# SendClient_Sheet.net
KiCad netlist of a schematic drawn in Altium Designer
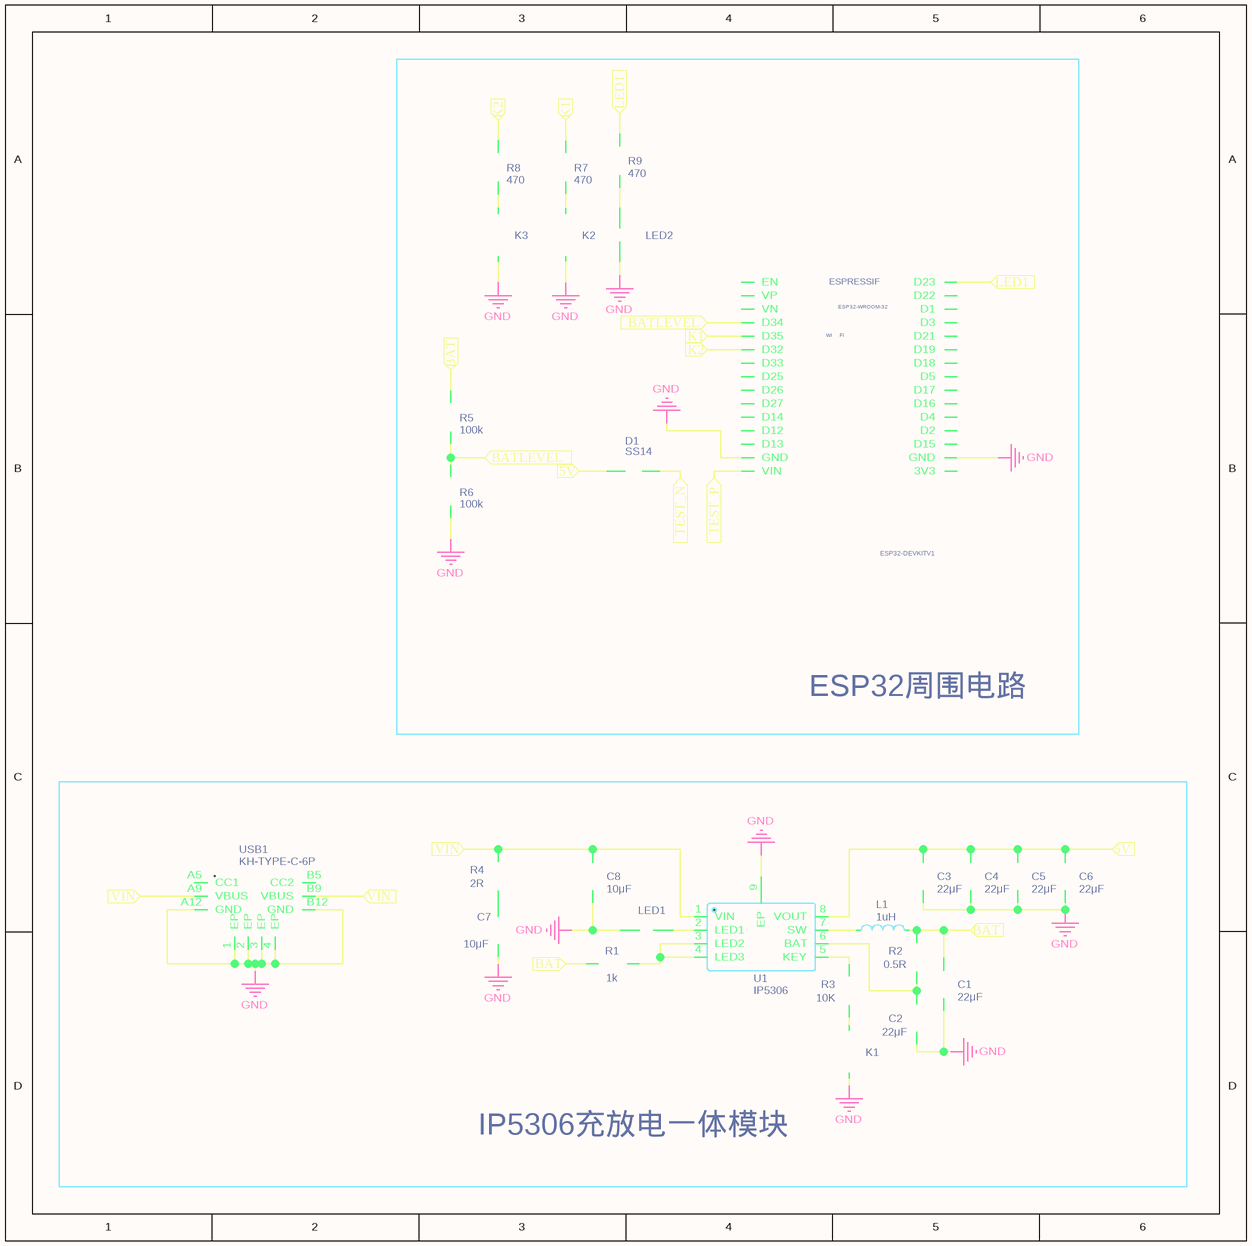
[diagram p0: SendClient_Sheet.schdoc]

(export (version "E")
  (design (tool "Eeschema 10.0.6"))
  (components
    (comp (ref "BOARD1")
      (value "ESP32DEVKITV1")
      (fields (field (name "CONTRIBUTOR") "radio"))
      (libsource (lib "altium-import") (part "root_0_ESP32DEVKITV1_"))
    )
    (comp (ref "C1")
      (value "22μF")
      (fields
        (field (name "BOM_SUPPLIER PART") "C338150")
        (field (name "BOM_MANUFACTURER PART") "0603B101K500CT")
        (field (name "CONTRIBUTOR") "LCSC")
      )
      (libsource (lib "altium-import") (part "root_3_22μF_"))
    )
    (comp (ref "C2")
      (value "22μF")
      (fields
        (field (name "BOM_SUPPLIER PART") "C338150")
        (field (name "BOM_MANUFACTURER PART") "0603B101K500CT")
        (field (name "CONTRIBUTOR") "LCSC")
      )
      (libsource (lib "altium-import") (part "root_3_22μF_"))
    )
    (comp (ref "C3")
      (value "22μF")
      (fields
        (field (name "BOM_SUPPLIER PART") "C338150")
        (field (name "BOM_MANUFACTURER PART") "0603B101K500CT")
        (field (name "CONTRIBUTOR") "LCSC")
      )
      (libsource (lib "altium-import") (part "root_3_22μF_"))
    )
    (comp (ref "C4")
      (value "22μF")
      (fields
        (field (name "BOM_SUPPLIER PART") "C338150")
        (field (name "BOM_MANUFACTURER PART") "0603B101K500CT")
        (field (name "CONTRIBUTOR") "LCSC")
      )
      (libsource (lib "altium-import") (part "root_3_22μF_"))
    )
    (comp (ref "C5")
      (value "22μF")
      (fields
        (field (name "BOM_SUPPLIER PART") "C338150")
        (field (name "BOM_MANUFACTURER PART") "0603B101K500CT")
        (field (name "CONTRIBUTOR") "LCSC")
      )
      (libsource (lib "altium-import") (part "root_3_22μF_"))
    )
    (comp (ref "C6")
      (value "22μF")
      (fields
        (field (name "BOM_SUPPLIER PART") "C338150")
        (field (name "BOM_MANUFACTURER PART") "0603B101K500CT")
        (field (name "CONTRIBUTOR") "LCSC")
      )
      (libsource (lib "altium-import") (part "root_3_22μF_"))
    )
    (comp (ref "C7")
      (value "10μF")
      (fields
        (field (name "BOM_SUPPLIER PART") "C338150")
        (field (name "BOM_MANUFACTURER PART") "0603B101K500CT")
        (field (name "CONTRIBUTOR") "LCSC")
      )
      (libsource (lib "altium-import") (part "root_3_10μF_"))
    )
    (comp (ref "C8")
      (value "10μF")
      (fields
        (field (name "BOM_SUPPLIER PART") "C338150")
        (field (name "BOM_MANUFACTURER PART") "0603B101K500CT")
        (field (name "CONTRIBUTOR") "LCSC")
      )
      (libsource (lib "altium-import") (part "root_3_10μF_"))
    )
    (comp (ref "D1")
      (value "SS14")
      (fields (field (name "BOM_SUPPLIER PART") "C2480"))
      (libsource (lib "altium-import") (part "root_2_SS14_"))
    )
    (comp (ref "K1")
      (value "BUTTON_FLASH")
      (fields (field (name "CONTRIBUTOR") "dingding1"))
      (libsource (lib "altium-import") (part "root_3_BUTTON_FLASH_"))
    )
    (comp (ref "K2")
      (value "BUTTON_FLASH")
      (fields (field (name "CONTRIBUTOR") "dingding1"))
      (libsource (lib "altium-import") (part "root_3_BUTTON_FLASH_"))
    )
    (comp (ref "K3")
      (value "BUTTON_FLASH")
      (fields (field (name "CONTRIBUTOR") "dingding1"))
      (libsource (lib "altium-import") (part "root_3_BUTTON_FLASH_"))
    )
    (comp (ref "L1")
      (value "1uH")
      (fields
        (field (name "BOM_SUPPLIER PART") "C436543")
        (field (name "BOM_MANUFACTURER PART") "PSPMAA0603-1R0M-ANF")
        (field (name "CONTRIBUTOR") "LCSC")
      )
      (libsource (lib "altium-import") (part "root_0_1uH_"))
    )
    (comp (ref "LED1")
      (value "LED-0603_R")
      (fields
        (field (name "BOM_MANUFACTURER PART") "19-217/R6C-AL1M2VY/3T")
        (field (name "BOM_SUPPLIER PART") "C72044")
        (field (name "CONTRIBUTOR") "LCEDA_01")
      )
      (libsource (lib "altium-import") (part "root_2_LED-0603_R_"))
    )
    (comp (ref "LED2")
      (value "LED-0603_R")
      (fields
        (field (name "BOM_MANUFACTURER PART") "19-217/R6C-AL1M2VY/3T")
        (field (name "BOM_SUPPLIER PART") "C72044")
        (field (name "CONTRIBUTOR") "LCEDA_01")
      )
      (libsource (lib "altium-import") (part "root_3_LED-0603_R_"))
    )
    (comp (ref "R1")
      (value "1k")
      (fields
        (field (name "BOM_MANUFACTURER PART") "RC0603JR-079K1L")
        (field (name "BOM_SUPPLIER PART") "C137602")
      )
      (libsource (lib "altium-import") (part "root_2_1k_"))
    )
    (comp (ref "R2")
      (value "0.5R")
      (fields
        (field (name "BOM_MANUFACTURER PART") "RC0603JR-079K1L")
        (field (name "BOM_SUPPLIER PART") "C137602")
      )
      (libsource (lib "altium-import") (part "root_3_0.5R_"))
    )
    (comp (ref "R3")
      (value "10K")
      (fields
        (field (name "BOM_MANUFACTURER PART") "RC0603JR-079K1L")
        (field (name "BOM_SUPPLIER PART") "C137602")
      )
      (libsource (lib "altium-import") (part "root_3_10K_"))
    )
    (comp (ref "R4")
      (value "2R")
      (fields
        (field (name "BOM_MANUFACTURER PART") "RC0603JR-079K1L")
        (field (name "BOM_SUPPLIER PART") "C137602")
      )
      (libsource (lib "altium-import") (part "root_3_2R_"))
    )
    (comp (ref "R5")
      (value "100k")
      (fields
        (field (name "BOM_MANUFACTURER PART") "RC0603JR-079K1L")
        (field (name "BOM_SUPPLIER PART") "C137602")
      )
      (libsource (lib "altium-import") (part "root_3_100k_"))
    )
    (comp (ref "R6")
      (value "100k")
      (fields
        (field (name "BOM_MANUFACTURER PART") "RC0603JR-079K1L")
        (field (name "BOM_SUPPLIER PART") "C137602")
      )
      (libsource (lib "altium-import") (part "root_3_100k_"))
    )
    (comp (ref "R7")
      (value "470")
      (fields
        (field (name "BOM_MANUFACTURER PART") "RC0603JR-079K1L")
        (field (name "BOM_SUPPLIER PART") "C137602")
      )
      (libsource (lib "altium-import") (part "root_1_470_"))
    )
    (comp (ref "R8")
      (value "470")
      (fields
        (field (name "BOM_MANUFACTURER PART") "RC0603JR-079K1L")
        (field (name "BOM_SUPPLIER PART") "C137602")
      )
      (libsource (lib "altium-import") (part "root_1_470_"))
    )
    (comp (ref "R9")
      (value "470")
      (fields
        (field (name "BOM_MANUFACTURER PART") "RC0603JR-079K1L")
        (field (name "BOM_SUPPLIER PART") "C137602")
      )
      (libsource (lib "altium-import") (part "root_1_470_"))
    )
    (comp (ref "U1")
      (value "IP5306")
      (fields (field (name "BOM_SUPPLIER PART") "C181692") (field (name "CONTRIBUTOR") "LCSC"))
      (libsource (lib "altium-import") (part "root_0_IP5306_"))
    )
    (comp (ref "USB1")
      (value "KH-TYPE-C-6P")
      (fields (field (name "BOM_SUPPLIER PART") "C709355") (field (name "CONTRIBUTOR") "LCSC"))
      (libsource (lib "altium-import") (part "root_0_KH-TYPE-C-6P_"))
    )
  )
  (nets
    (net (code "1") (name "/5V") (class "Default")
      (node (ref "C3") (pin "2") (pinfunction "2_2") (pintype "passive"))
      (node (ref "C4") (pin "2") (pinfunction "2_2") (pintype "passive"))
      (node (ref "C5") (pin "2") (pinfunction "2_2") (pintype "passive"))
      (node (ref "C6") (pin "2") (pinfunction "2_2") (pintype "passive"))
      (node (ref "D1") (pin "2") (pinfunction "A_2") (pintype "passive"))
      (node (ref "U1") (pin "8") (pinfunction "VOUT_8") (pintype "passive"))
    )
    (net (code "2") (name "/BAT") (class "Default")
      (node (ref "C1") (pin "2") (pinfunction "2_2") (pintype "passive"))
      (node (ref "L1") (pin "2") (pinfunction "2_2") (pintype "passive"))
      (node (ref "R1") (pin "2") (pinfunction "2_2") (pintype "passive"))
      (node (ref "R2") (pin "1") (pinfunction "1_1") (pintype "passive"))
      (node (ref "R5") (pin "1") (pinfunction "1_1") (pintype "passive"))
    )
    (net (code "3") (name "/BATLEVEL") (class "Default")
      (node (ref "BOARD1") (pin "D34") (pinfunction "D34_D34") (pintype "passive"))
      (node (ref "R5") (pin "2") (pinfunction "2_2") (pintype "passive"))
      (node (ref "R6") (pin "1") (pinfunction "1_1") (pintype "passive"))
    )
    (net (code "4") (name "/K1") (class "Default")
      (node (ref "BOARD1") (pin "D35") (pinfunction "D35_D35") (pintype "passive"))
      (node (ref "R7") (pin "2") (pinfunction "2_2") (pintype "passive"))
    )
    (net (code "5") (name "/K2") (class "Default")
      (node (ref "BOARD1") (pin "D32") (pinfunction "D32_D32") (pintype "passive"))
      (node (ref "R8") (pin "2") (pinfunction "2_2") (pintype "passive"))
    )
    (net (code "6") (name "/LED1") (class "Default")
      (node (ref "BOARD1") (pin "D23") (pinfunction "D23_D23") (pintype "passive"))
      (node (ref "R9") (pin "2") (pinfunction "2_2") (pintype "passive"))
    )
    (net (code "7") (name "/TEST_N") (class "Default")
      (node (ref "D1") (pin "1") (pinfunction "K_1") (pintype "passive"))
    )
    (net (code "8") (name "/TEST_P") (class "Default")
      (node (ref "BOARD1") (pin "VIN") (pinfunction "VIN_VIN") (pintype "passive"))
    )
    (net (code "9") (name "/VIN") (class "Default")
      (node (ref "C8") (pin "2") (pinfunction "2_2") (pintype "passive"))
      (node (ref "R4") (pin "1") (pinfunction "1_1") (pintype "passive"))
      (node (ref "U1") (pin "1") (pinfunction "VIN_1") (pintype "passive"))
      (node (ref "USB1") (pin "A9") (pinfunction "VBUS_A9") (pintype "passive"))
      (node (ref "USB1") (pin "B9") (pinfunction "VBUS_B9") (pintype "passive"))
    )
    (net (code "10") (name "GND") (class "Default")
      (node (ref "BOARD1") (pin "GND") (pinfunction "GND_GND") (pintype "passive"))
      (node (ref "BOARD1") (pin "GND@1") (pinfunction "GND_GND@1") (pintype "passive"))
      (node (ref "C1") (pin "1") (pinfunction "1_1") (pintype "passive"))
      (node (ref "C2") (pin "1") (pinfunction "1_1") (pintype "passive"))
      (node (ref "C3") (pin "1") (pinfunction "1_1") (pintype "passive"))
      (node (ref "C4") (pin "1") (pinfunction "1_1") (pintype "passive"))
      (node (ref "C5") (pin "1") (pinfunction "1_1") (pintype "passive"))
      (node (ref "C6") (pin "1") (pinfunction "1_1") (pintype "passive"))
      (node (ref "C7") (pin "1") (pinfunction "1_1") (pintype "passive"))
      (node (ref "C8") (pin "1") (pinfunction "1_1") (pintype "passive"))
      (node (ref "K1") (pin "2") (pinfunction "2_2") (pintype "passive"))
      (node (ref "K2") (pin "2") (pinfunction "2_2") (pintype "passive"))
      (node (ref "K3") (pin "2") (pinfunction "2_2") (pintype "passive"))
      (node (ref "LED1") (pin "2") (pinfunction "2_2") (pintype "passive"))
      (node (ref "LED2") (pin "2") (pinfunction "2_2") (pintype "passive"))
      (node (ref "R6") (pin "2") (pinfunction "2_2") (pintype "passive"))
      (node (ref "U1") (pin "9") (pinfunction "EP_9") (pintype "passive"))
      (node (ref "USB1") (pin "1") (pinfunction "EP_1") (pintype "passive"))
      (node (ref "USB1") (pin "2") (pinfunction "EP_2") (pintype "passive"))
      (node (ref "USB1") (pin "3") (pinfunction "EP_3") (pintype "passive"))
      (node (ref "USB1") (pin "4") (pinfunction "EP_4") (pintype "passive"))
      (node (ref "USB1") (pin "A12") (pinfunction "GND_A12") (pintype "passive"))
      (node (ref "USB1") (pin "B12") (pinfunction "GND_B12") (pintype "passive"))
    )
    (net (code "11") (name "Net-(C7-Pad2)") (class "Default")
      (node (ref "C7") (pin "2") (pinfunction "2_2") (pintype "passive"))
      (node (ref "R4") (pin "2") (pinfunction "2_2") (pintype "passive"))
    )
    (net (code "12") (name "Net-(K1-Pad1)") (class "Default")
      (node (ref "K1") (pin "1") (pinfunction "1_1") (pintype "passive"))
      (node (ref "R3") (pin "2") (pinfunction "2_2") (pintype "passive"))
    )
    (net (code "13") (name "Net-(K2-Pad1)") (class "Default")
      (node (ref "K2") (pin "1") (pinfunction "1_1") (pintype "passive"))
      (node (ref "R7") (pin "1") (pinfunction "1_1") (pintype "passive"))
    )
    (net (code "14") (name "Net-(K3-Pad1)") (class "Default")
      (node (ref "K3") (pin "1") (pinfunction "1_1") (pintype "passive"))
      (node (ref "R8") (pin "1") (pinfunction "1_1") (pintype "passive"))
    )
    (net (code "15") (name "Net-(LED2-Pad1)") (class "Default")
      (node (ref "LED2") (pin "1") (pinfunction "1_1") (pintype "passive"))
      (node (ref "R9") (pin "1") (pinfunction "1_1") (pintype "passive"))
    )
    (net (code "16") (name "Net-(U1-BAT)") (class "Default")
      (node (ref "C2") (pin "2") (pinfunction "2_2") (pintype "passive"))
      (node (ref "R2") (pin "2") (pinfunction "2_2") (pintype "passive"))
      (node (ref "U1") (pin "6") (pinfunction "BAT_6") (pintype "passive"))
    )
    (net (code "17") (name "Net-(U1-KEY)") (class "Default")
      (node (ref "R3") (pin "1") (pinfunction "1_1") (pintype "passive"))
      (node (ref "U1") (pin "5") (pinfunction "KEY_5") (pintype "passive"))
    )
    (net (code "18") (name "Net-(U1-LED1)") (class "Default")
      (node (ref "LED1") (pin "1") (pinfunction "1_1") (pintype "passive"))
      (node (ref "U1") (pin "2") (pinfunction "LED1_2") (pintype "passive"))
    )
    (net (code "19") (name "Net-(U1-LED2)") (class "Default")
      (node (ref "R1") (pin "1") (pinfunction "1_1") (pintype "passive"))
      (node (ref "U1") (pin "3") (pinfunction "LED2_3") (pintype "passive"))
      (node (ref "U1") (pin "4") (pinfunction "LED3_4") (pintype "passive"))
    )
    (net (code "20") (name "Net-(U1-SW)") (class "Default")
      (node (ref "L1") (pin "1") (pinfunction "1_1") (pintype "passive"))
      (node (ref "U1") (pin "7") (pinfunction "SW_7") (pintype "passive"))
    )
    (net (code "21") (name "unconnected-(BOARD1-Pad3V3)") (class "Default")
      (node (ref "BOARD1") (pin "3V3") (pinfunction "3V3_3V3") (pintype "passive"))
    )
    (net (code "22") (name "unconnected-(BOARD1-PadD1)") (class "Default")
      (node (ref "BOARD1") (pin "D1") (pinfunction "D1_D1") (pintype "passive"))
    )
    (net (code "23") (name "unconnected-(BOARD1-PadD2)") (class "Default")
      (node (ref "BOARD1") (pin "D2") (pinfunction "D2_D2") (pintype "passive"))
    )
    (net (code "24") (name "unconnected-(BOARD1-PadD3)") (class "Default")
      (node (ref "BOARD1") (pin "D3") (pinfunction "D3_D3") (pintype "passive"))
    )
    (net (code "25") (name "unconnected-(BOARD1-PadD4)") (class "Default")
      (node (ref "BOARD1") (pin "D4") (pinfunction "D4_D4") (pintype "passive"))
    )
    (net (code "26") (name "unconnected-(BOARD1-PadD5)") (class "Default")
      (node (ref "BOARD1") (pin "D5") (pinfunction "D5_D5") (pintype "passive"))
    )
    (net (code "27") (name "unconnected-(BOARD1-PadD12)") (class "Default")
      (node (ref "BOARD1") (pin "D12") (pinfunction "D12_D12") (pintype "passive"))
    )
    (net (code "28") (name "unconnected-(BOARD1-PadD13)") (class "Default")
      (node (ref "BOARD1") (pin "D13") (pinfunction "D13_D13") (pintype "passive"))
    )
    (net (code "29") (name "unconnected-(BOARD1-PadD14)") (class "Default")
      (node (ref "BOARD1") (pin "D14") (pinfunction "D14_D14") (pintype "passive"))
    )
    (net (code "30") (name "unconnected-(BOARD1-PadD15)") (class "Default")
      (node (ref "BOARD1") (pin "D15") (pinfunction "D15_D15") (pintype "passive"))
    )
    (net (code "31") (name "unconnected-(BOARD1-PadD16)") (class "Default")
      (node (ref "BOARD1") (pin "D16") (pinfunction "D16_D16") (pintype "passive"))
    )
    (net (code "32") (name "unconnected-(BOARD1-PadD17)") (class "Default")
      (node (ref "BOARD1") (pin "D17") (pinfunction "D17_D17") (pintype "passive"))
    )
    (net (code "33") (name "unconnected-(BOARD1-PadD18)") (class "Default")
      (node (ref "BOARD1") (pin "D18") (pinfunction "D18_D18") (pintype "passive"))
    )
    (net (code "34") (name "unconnected-(BOARD1-PadD19)") (class "Default")
      (node (ref "BOARD1") (pin "D19") (pinfunction "D19_D19") (pintype "passive"))
    )
    (net (code "35") (name "unconnected-(BOARD1-PadD21)") (class "Default")
      (node (ref "BOARD1") (pin "D21") (pinfunction "D21_D21") (pintype "passive"))
    )
    (net (code "36") (name "unconnected-(BOARD1-PadD22)") (class "Default")
      (node (ref "BOARD1") (pin "D22") (pinfunction "D22_D22") (pintype "passive"))
    )
    (net (code "37") (name "unconnected-(BOARD1-PadD25)") (class "Default")
      (node (ref "BOARD1") (pin "D25") (pinfunction "D25_D25") (pintype "passive"))
    )
    (net (code "38") (name "unconnected-(BOARD1-PadD26)") (class "Default")
      (node (ref "BOARD1") (pin "D26") (pinfunction "D26_D26") (pintype "passive"))
    )
    (net (code "39") (name "unconnected-(BOARD1-PadD27)") (class "Default")
      (node (ref "BOARD1") (pin "D27") (pinfunction "D27_D27") (pintype "passive"))
    )
    (net (code "40") (name "unconnected-(BOARD1-PadD33)") (class "Default")
      (node (ref "BOARD1") (pin "D33") (pinfunction "D33_D33") (pintype "passive"))
    )
    (net (code "41") (name "unconnected-(BOARD1-PadEN)") (class "Default")
      (node (ref "BOARD1") (pin "EN") (pinfunction "EN_EN") (pintype "passive"))
    )
    (net (code "42") (name "unconnected-(BOARD1-PadVN)") (class "Default")
      (node (ref "BOARD1") (pin "VN") (pinfunction "VN_VN") (pintype "passive"))
    )
    (net (code "43") (name "unconnected-(BOARD1-PadVP)") (class "Default")
      (node (ref "BOARD1") (pin "VP") (pinfunction "VP_VP") (pintype "passive"))
    )
    (net (code "44") (name "unconnected-(USB1-CC1-PadA5)") (class "Default")
      (node (ref "USB1") (pin "A5") (pinfunction "CC1_A5") (pintype "passive"))
    )
    (net (code "45") (name "unconnected-(USB1-CC2-PadB5)") (class "Default")
      (node (ref "USB1") (pin "B5") (pinfunction "CC2_B5") (pintype "passive"))
    )
  )
)
